# UC3842_-_SIN_TEST_GENERA_MODELO.net
KiCad netlist of a schematic drawn in Altium Designer
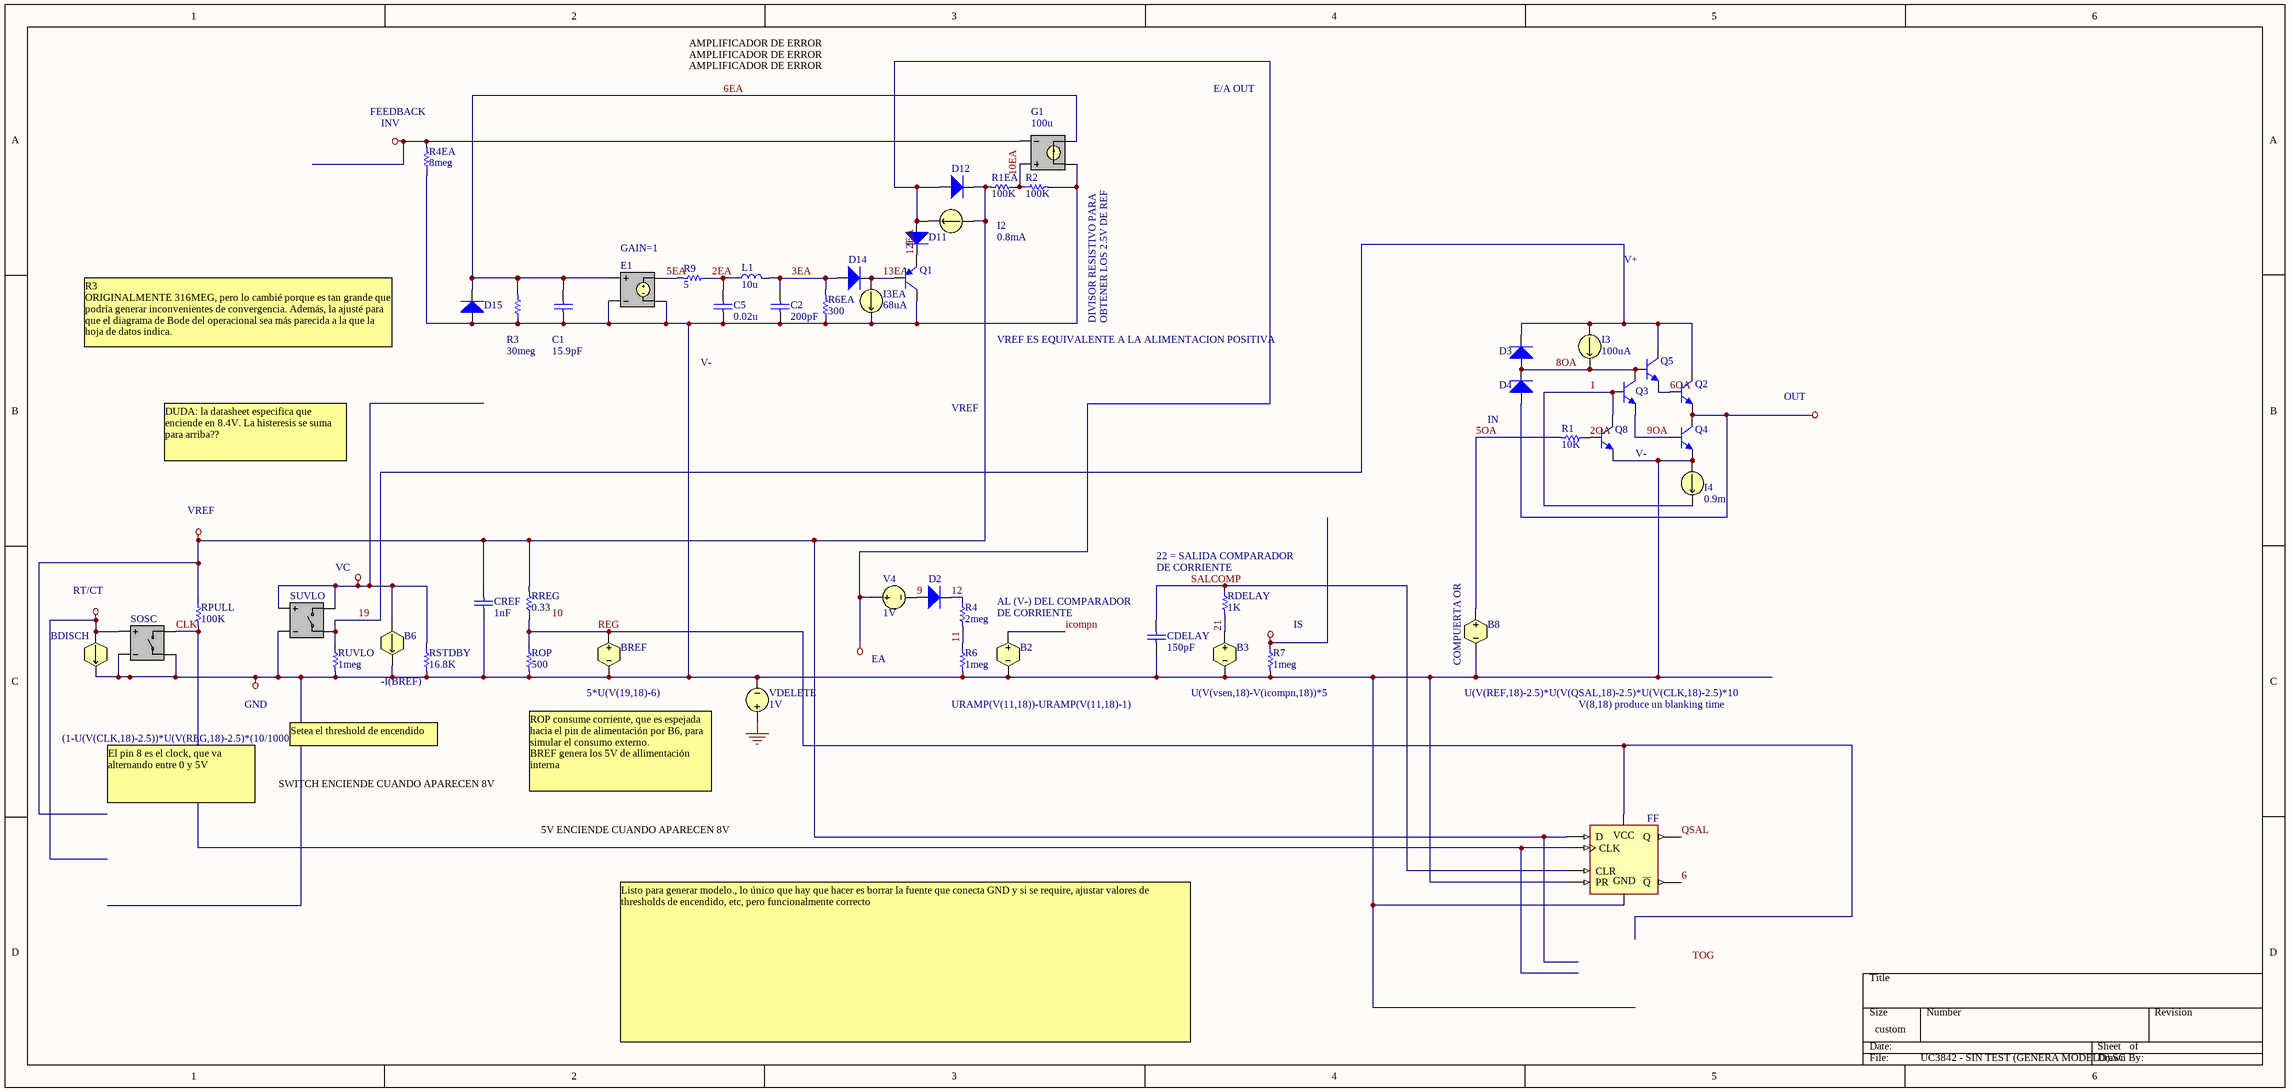
[diagram p0: UC3842 - SIN TEST (GENERA MODELO).SCHDOC]

(export (version "E")
  (design (tool "Eeschema 10.0.6"))
  (components
    (comp (ref "B2")
      (value "BVSRC")
      (description "Non-Linear Dependent Voltage Source")
      (fields
        (field (name "EQUATION") "URAMP(V(11,18))-URAMP(V(11,18)-1)")
        (field (name "PUBLISHER") "Altium Limited")
      )
      (libsource (lib "Simulation Sources") (part "BVSRC"))
    )
    (comp (ref "B3")
      (value "BVSRC")
      (description "Non-Linear Dependent Voltage Source")
      (fields
        (field (name "EQUATION") "U(V(vsen,18)-V(icompn,18))*5")
        (field (name "PUBLISHER") "Altium Limited")
      )
      (libsource (lib "Simulation Sources") (part "BVSRC"))
    )
    (comp (ref "B6")
      (value "BISRC")
      (description "Non-Linear Dependent Current Source")
      (fields (field (name "EQUATION") "-I(BREF)") (field (name "PUBLISHER") "Altium Limited"))
      (libsource (lib "Simulation Sources") (part "BISRC"))
    )
    (comp (ref "B8")
      (value "BVSRC")
      (description "Non-Linear Dependent Voltage Source")
      (fields
        (field (name "EQUATION") "U(V(REF,18)-2.5)*U(V(QSAL,18)-2.5)*U(V(CLK,18)-2.5)*10")
        (field (name "PUBLISHER") "Altium Limited")
      )
      (libsource (lib "Simulation Sources") (part "BVSRC"))
    )
    (comp (ref "BDISCH")
      (value "BISRC")
      (description "Non-Linear Dependent Current Source")
      (fields
        (field (name "EQUATION") "(1-U(V(CLK,18)-2.5))*U(V(REG,18)-2.5)*(10/1000)")
        (field (name "PUBLISHER") "Altium Limited")
      )
      (libsource (lib "Simulation Sources") (part "BISRC"))
    )
    (comp (ref "BREF")
      (value "BVSRC")
      (description "Non-Linear Dependent Voltage Source")
      (fields (field (name "EQUATION") "5*U(V(19,18)-6)") (field (name "PUBLISHER") "Altium Limited"))
      (libsource (lib "Simulation Sources") (part "BVSRC"))
    )
    (comp (ref "C1")
      (value "15.9pF")
      (footprint "0805")
      (description "Capacitor")
      (fields (field (name "VOLTAGE") "50V") (field (name "Comment") "Cap"))
      (libsource (lib "FEDE") (part "Cap"))
    )
    (comp (ref "C2")
      (value "200pF")
      (footprint "0805")
      (description "Capacitor")
      (fields (field (name "VOLTAGE") "50V") (field (name "Comment") "Cap"))
      (libsource (lib "FEDE") (part "Cap"))
    )
    (comp (ref "C5")
      (value "0.02u")
      (footprint "0805")
      (description "Capacitor")
      (fields (field (name "VOLTAGE") "50V") (field (name "Comment") "Cap"))
      (libsource (lib "FEDE") (part "Cap"))
    )
    (comp (ref "CDELAY")
      (value "150pF")
      (footprint "0805")
      (description "Capacitor")
      (fields (field (name "VOLTAGE") "50V") (field (name "Comment") "Cap"))
      (libsource (lib "FEDE") (part "Cap"))
    )
    (comp (ref "CREF")
      (value "1nF")
      (footprint "0805")
      (description "Capacitor")
      (fields (field (name "VOLTAGE") "50V") (field (name "Comment") "Cap"))
      (libsource (lib "FEDE") (part "Cap"))
    )
    (comp (ref "D2")
      (value "Diode")
      (footprint "diode400")
      (description "Diodo")
      (libsource (lib "FEDE") (part "Diode"))
    )
    (comp (ref "D3")
      (value "Diode")
      (footprint "diode400")
      (description "Diodo")
      (libsource (lib "FEDE") (part "Diode"))
    )
    (comp (ref "D4")
      (value "Diode")
      (footprint "diode400")
      (description "Diodo")
      (libsource (lib "FEDE") (part "Diode"))
    )
    (comp (ref "D11")
      (value "Diode")
      (footprint "diode400")
      (description "Diodo")
      (libsource (lib "FEDE") (part "Diode"))
    )
    (comp (ref "D12")
      (value "Diode")
      (footprint "diode400")
      (description "Diodo")
      (libsource (lib "FEDE") (part "Diode"))
    )
    (comp (ref "D14")
      (value "Diode")
      (footprint "diode400")
      (description "Diodo")
      (libsource (lib "FEDE") (part "Diode"))
    )
    (comp (ref "D15")
      (value "Diode")
      (footprint "diode400")
      (description "Diodo")
      (libsource (lib "FEDE") (part "Diode"))
    )
    (comp (ref "E1")
      (value "ESRC")
      (description "Voltage Controlled Voltage Source")
      (fields (field (name "PUBLISHER") "Altium Limited"))
      (libsource (lib "Simulation Sources") (part "ESRC"))
    )
    (comp (ref "FF")
      (value "FFSRV2")
      (description "D-Type Positive-Edge-Triggered Flip-Flop with Clear and Preset (simulación)")
      (libsource (lib "FEDE") (part "FFSRV2"))
    )
    (comp (ref "G1")
      (value "GSRC")
      (description "Voltage Controlled Current Source")
      (fields (field (name "GAIN") "100u") (field (name "PUBLISHER") "Altium Limited"))
      (libsource (lib "Simulation Sources") (part "GSRC"))
    )
    (comp (ref "I2")
      (value "0.8mA")
      (description "Current Source")
      (fields (field (name "Comment") "ISRC") (field (name "PUBLISHER") "Altium Limited"))
      (libsource (lib "Simulation Sources") (part "ISRC"))
    )
    (comp (ref "I3")
      (value "100uA")
      (description "Current Source")
      (fields (field (name "Comment") "ISRC") (field (name "PUBLISHER") "Altium Limited"))
      (libsource (lib "Simulation Sources") (part "ISRC"))
    )
    (comp (ref "I3EA")
      (value "68uA")
      (description "Current Source")
      (fields (field (name "Comment") "ISRC") (field (name "PUBLISHER") "Altium Limited"))
      (libsource (lib "Simulation Sources") (part "ISRC"))
    )
    (comp (ref "I4")
      (value "0.9m")
      (description "Current Source")
      (fields (field (name "Comment") "ISRC") (field (name "PUBLISHER") "Altium Limited"))
      (libsource (lib "Simulation Sources") (part "ISRC"))
    )
    (comp (ref "L1")
      (value "10u")
      (footprint "TOROIDE TN14-9-5")
      (description "Inductor")
      (fields (field (name "Comment") "Inductor2"))
      (libsource (lib "FEDE") (part "Inductor2"))
    )
    (comp (ref "Q1")
      (value "PNP")
      (footprint "SOT23")
      (description "PNP Bipolar Transistor")
      (libsource (lib "FEDE") (part "PNP"))
    )
    (comp (ref "Q2")
      (value "NPN")
      (footprint "SOT23")
      (description "NPN Bipolar Transistor")
      (libsource (lib "FEDE") (part "NPN"))
    )
    (comp (ref "Q3")
      (value "NPN")
      (footprint "SOT23")
      (description "NPN Bipolar Transistor")
      (libsource (lib "FEDE") (part "NPN"))
    )
    (comp (ref "Q4")
      (value "NPN")
      (footprint "SOT23")
      (description "NPN Bipolar Transistor")
      (libsource (lib "FEDE") (part "NPN"))
    )
    (comp (ref "Q5")
      (value "NPN")
      (footprint "SOT23")
      (description "NPN Bipolar Transistor")
      (libsource (lib "FEDE") (part "NPN"))
    )
    (comp (ref "Q8")
      (value "NPN")
      (footprint "SOT23")
      (description "NPN Bipolar Transistor")
      (libsource (lib "FEDE") (part "NPN"))
    )
    (comp (ref "R1")
      (value "10K")
      (footprint "0805")
      (description "Resistor")
      (fields (field (name "POWER") "0.25W") (field (name "Comment") "Res"))
      (libsource (lib "FEDE") (part "Res"))
    )
    (comp (ref "R1EA")
      (value "100K")
      (footprint "0805")
      (description "Resistor")
      (fields (field (name "POWER") "0.25W") (field (name "Comment") "Res"))
      (libsource (lib "FEDE") (part "Res"))
    )
    (comp (ref "R2")
      (value "100K")
      (footprint "0805")
      (description "Resistor")
      (fields (field (name "POWER") "0.25W") (field (name "Comment") "Res"))
      (libsource (lib "FEDE") (part "Res"))
    )
    (comp (ref "R3")
      (value "30meg")
      (footprint "0805")
      (description "Resistor")
      (fields (field (name "POWER") "0.25W") (field (name "Comment") "Res"))
      (libsource (lib "FEDE") (part "Res"))
    )
    (comp (ref "R4")
      (value "2meg")
      (footprint "0805")
      (description "Resistor")
      (fields (field (name "POWER") "0.25W") (field (name "Comment") "Res"))
      (libsource (lib "FEDE") (part "Res"))
    )
    (comp (ref "R4EA")
      (value "8meg")
      (footprint "0805")
      (description "Resistor")
      (fields (field (name "POWER") "0.25W") (field (name "Comment") "Res"))
      (libsource (lib "FEDE") (part "Res"))
    )
    (comp (ref "R6")
      (value "1meg")
      (footprint "0805")
      (description "Resistor")
      (fields (field (name "POWER") "0.25W") (field (name "Comment") "Res"))
      (libsource (lib "FEDE") (part "Res"))
    )
    (comp (ref "R6EA")
      (value "300")
      (footprint "0805")
      (description "Resistor")
      (fields (field (name "POWER") "0.25W") (field (name "Comment") "Res"))
      (libsource (lib "FEDE") (part "Res"))
    )
    (comp (ref "R7")
      (value "1meg")
      (footprint "0805")
      (description "Resistor")
      (fields (field (name "POWER") "0.25W") (field (name "Comment") "Res"))
      (libsource (lib "FEDE") (part "Res"))
    )
    (comp (ref "R9")
      (value "5")
      (footprint "0805")
      (description "Resistor")
      (fields (field (name "POWER") "0.25W") (field (name "Comment") "Res"))
      (libsource (lib "FEDE") (part "Res"))
    )
    (comp (ref "RDELAY")
      (value "1K")
      (footprint "0805")
      (description "Resistor")
      (fields (field (name "POWER") "0.25W") (field (name "Comment") "Res"))
      (libsource (lib "FEDE") (part "Res"))
    )
    (comp (ref "ROP")
      (value "500")
      (footprint "0805")
      (description "Resistor")
      (fields (field (name "POWER") "0.25W") (field (name "Comment") "Res"))
      (libsource (lib "FEDE") (part "Res"))
    )
    (comp (ref "RPULL")
      (value "100K")
      (footprint "0805")
      (description "Resistor")
      (fields (field (name "POWER") "0.25W") (field (name "Comment") "Res"))
      (libsource (lib "FEDE") (part "Res"))
    )
    (comp (ref "RREG")
      (value "0.33")
      (footprint "0805")
      (description "Resistor")
      (fields (field (name "POWER") "0.25W") (field (name "Comment") "Res"))
      (libsource (lib "FEDE") (part "Res"))
    )
    (comp (ref "RSTDBY")
      (value "16.8K")
      (footprint "0805")
      (description "Resistor")
      (fields (field (name "POWER") "0.25W") (field (name "Comment") "Res"))
      (libsource (lib "FEDE") (part "Res"))
    )
    (comp (ref "RUVLO")
      (value "1meg")
      (footprint "0805")
      (description "Resistor")
      (fields (field (name "POWER") "0.25W") (field (name "Comment") "Res"))
      (libsource (lib "FEDE") (part "Res"))
    )
    (comp (ref "SOSC")
      (value "VSW")
      (description "Voltage Controlled Switch (simulación)")
      (libsource (lib "FEDE") (part "VSW"))
    )
    (comp (ref "SUVLO")
      (value "VSW")
      (description "Voltage Controlled Switch (simulación)")
      (libsource (lib "FEDE") (part "VSW"))
    )
    (comp (ref "V4")
      (value "1V")
      (description "Voltage Source")
      (fields (field (name "Comment") "VSRC") (field (name "PUBLISHER") "Altium Limited"))
      (libsource (lib "Simulation Sources") (part "VSRC"))
    )
    (comp (ref "VDELETE")
      (value "1V")
      (description "Voltage Source")
      (fields (field (name "Comment") "VSRC") (field (name "PUBLISHER") "Altium Limited"))
      (libsource (lib "Simulation Sources") (part "VSRC"))
    )
  )
  (nets
    (net (code "1") (name "/1") (class "Default")
      (node (ref "I4") (pin "2") (pinfunction "2_2") (pintype "passive"))
      (node (ref "Q3") (pin "2") (pinfunction "B_2") (pintype "passive"))
      (node (ref "Q8") (pin "1") (pinfunction "C_1") (pintype "passive"))
    )
    (net (code "2") (name "/2EA") (class "Default")
      (node (ref "C5") (pin "2") (pinfunction "2_2") (pintype "passive"))
      (node (ref "L1") (pin "1") (pinfunction "1_1") (pintype "passive"))
      (node (ref "R9") (pin "1") (pinfunction "1_1") (pintype "passive"))
    )
    (net (code "3") (name "/2OA") (class "Default")
      (node (ref "Q8") (pin "2") (pinfunction "B_2") (pintype "passive"))
      (node (ref "R1") (pin "1") (pinfunction "1_1") (pintype "passive"))
    )
    (net (code "4") (name "/3EA") (class "Default")
      (node (ref "C2") (pin "2") (pinfunction "2_2") (pintype "passive"))
      (node (ref "D14") (pin "1") (pinfunction "1_1") (pintype "passive"))
      (node (ref "L1") (pin "2") (pinfunction "2_2") (pintype "passive"))
      (node (ref "R6EA") (pin "2") (pinfunction "2_2") (pintype "passive"))
    )
    (net (code "5") (name "/5EA") (class "Default")
      (node (ref "E1") (pin "3") (pinfunction "N+_3") (pintype "passive"))
      (node (ref "R9") (pin "2") (pinfunction "2_2") (pintype "passive"))
    )
    (net (code "6") (name "/5OA") (class "Default")
      (node (ref "B8") (pin "1") (pinfunction "1_1") (pintype "passive"))
      (node (ref "R1") (pin "2") (pinfunction "2_2") (pintype "passive"))
    )
    (net (code "7") (name "/6") (class "Default")
      (node (ref "FF") (pin "6") (pinfunction "~{Q}_6") (pintype "output"))
    )
    (net (code "8") (name "/6EA") (class "Default")
      (node (ref "C1") (pin "2") (pinfunction "2_2") (pintype "passive"))
      (node (ref "D15") (pin "2") (pinfunction "2_2") (pintype "passive"))
      (node (ref "E1") (pin "1") (pinfunction "NC+_1") (pintype "passive"))
      (node (ref "G1") (pin "4") (pinfunction "N-_4") (pintype "passive"))
      (node (ref "R3") (pin "2") (pinfunction "2_2") (pintype "passive"))
    )
    (net (code "9") (name "/6OA") (class "Default")
      (node (ref "Q2") (pin "2") (pinfunction "B_2") (pintype "passive"))
      (node (ref "Q5") (pin "3") (pinfunction "E_3") (pintype "passive"))
    )
    (net (code "10") (name "/8OA") (class "Default")
      (node (ref "D3") (pin "1") (pinfunction "1_1") (pintype "passive"))
      (node (ref "D4") (pin "2") (pinfunction "2_2") (pintype "passive"))
      (node (ref "I3") (pin "2") (pinfunction "2_2") (pintype "passive"))
      (node (ref "Q3") (pin "1") (pinfunction "C_1") (pintype "passive"))
      (node (ref "Q5") (pin "2") (pinfunction "B_2") (pintype "passive"))
    )
    (net (code "11") (name "/9") (class "Default")
      (node (ref "D2") (pin "1") (pinfunction "1_1") (pintype "passive"))
      (node (ref "V4") (pin "2") (pinfunction "2_2") (pintype "passive"))
    )
    (net (code "12") (name "/9OA") (class "Default")
      (node (ref "Q3") (pin "3") (pinfunction "E_3") (pintype "passive"))
      (node (ref "Q4") (pin "2") (pinfunction "B_2") (pintype "passive"))
    )
    (net (code "14") (name "/10EA") (class "Default")
      (node (ref "G1") (pin "1") (pinfunction "NC+_1") (pintype "passive"))
      (node (ref "R1EA") (pin "1") (pinfunction "1_1") (pintype "passive"))
      (node (ref "R2") (pin "1") (pinfunction "1_1") (pintype "passive"))
    )
    (net (code "15") (name "/11") (class "Default")
      (node (ref "R4") (pin "2") (pinfunction "2_2") (pintype "passive"))
      (node (ref "R6") (pin "1") (pinfunction "1_1") (pintype "passive"))
    )
    (net (code "16") (name "/12") (class "Default")
      (node (ref "D2") (pin "2") (pinfunction "2_2") (pintype "passive"))
      (node (ref "R4") (pin "1") (pinfunction "1_1") (pintype "passive"))
    )
    (net (code "17") (name "/12EA") (class "Default")
      (node (ref "D11") (pin "2") (pinfunction "2_2") (pintype "passive"))
      (node (ref "Q1") (pin "3") (pinfunction "E_3") (pintype "passive"))
    )
    (net (code "18") (name "/13EA") (class "Default")
      (node (ref "D14") (pin "2") (pinfunction "2_2") (pintype "passive"))
      (node (ref "I3EA") (pin "1") (pinfunction "1_1") (pintype "passive"))
      (node (ref "Q1") (pin "2") (pinfunction "B_2") (pintype "passive"))
    )
    (net (code "19") (name "/19") (class "Default")
      (node (ref "D3") (pin "2") (pinfunction "2_2") (pintype "passive"))
      (node (ref "I3") (pin "1") (pinfunction "1_1") (pintype "passive"))
      (node (ref "Q2") (pin "1") (pinfunction "C_1") (pintype "passive"))
      (node (ref "Q5") (pin "1") (pinfunction "C_1") (pintype "passive"))
      (node (ref "RUVLO") (pin "1") (pinfunction "1_1") (pintype "passive"))
      (node (ref "SUVLO") (pin "4") (pinfunction "N2-_4") (pintype "passive"))
    )
    (net (code "20") (name "/21") (class "Default")
      (node (ref "B3") (pin "1") (pinfunction "1_1") (pintype "passive"))
      (node (ref "RDELAY") (pin "2") (pinfunction "2_2") (pintype "passive"))
    )
    (net (code "21") (name "/CLK") (class "Default")
      (node (ref "FF") (pin "3") (pinfunction "CLK_3") (pintype "input"))
      (node (ref "RPULL") (pin "2") (pinfunction "2_2") (pintype "passive"))
      (node (ref "SOSC") (pin "3") (pinfunction "N2+_3") (pintype "passive"))
    )
    (net (code "22") (name "/QSAL") (class "Default")
      (node (ref "FF") (pin "5") (pinfunction "Q_5") (pintype "output"))
    )
    (net (code "23") (name "/REG") (class "Default")
      (node (ref "BREF") (pin "1") (pinfunction "1_1") (pintype "passive"))
      (node (ref "FF") (pin "14") (pinfunction "VCC_14") (pintype "power_in"))
      (node (ref "ROP") (pin "1") (pinfunction "1_1") (pintype "passive"))
      (node (ref "RREG") (pin "1") (pinfunction "1_1") (pintype "passive"))
    )
    (net (code "24") (name "/SALCOMP") (class "Default")
      (node (ref "CDELAY") (pin "2") (pinfunction "2_2") (pintype "passive"))
      (node (ref "FF") (pin "1") (pinfunction "CLR_1") (pintype "input"))
      (node (ref "RDELAY") (pin "1") (pinfunction "1_1") (pintype "passive"))
    )
    (net (code "26") (name "/icompn") (class "Default")
      (node (ref "B2") (pin "1") (pinfunction "1_1") (pintype "passive"))
    )
    (net (code "27") (name "18") (class "Default")
      (node (ref "B2") (pin "2") (pinfunction "2_2") (pintype "passive"))
      (node (ref "B3") (pin "2") (pinfunction "2_2") (pintype "passive"))
      (node (ref "B6") (pin "2") (pinfunction "2_2") (pintype "passive"))
      (node (ref "B8") (pin "2") (pinfunction "2_2") (pintype "passive"))
      (node (ref "BDISCH") (pin "2") (pinfunction "2_2") (pintype "passive"))
      (node (ref "BREF") (pin "2") (pinfunction "2_2") (pintype "passive"))
      (node (ref "C1") (pin "1") (pinfunction "1_1") (pintype "passive"))
      (node (ref "C2") (pin "1") (pinfunction "1_1") (pintype "passive"))
      (node (ref "C5") (pin "1") (pinfunction "1_1") (pintype "passive"))
      (node (ref "CDELAY") (pin "1") (pinfunction "1_1") (pintype "passive"))
      (node (ref "CREF") (pin "1") (pinfunction "1_1") (pintype "passive"))
      (node (ref "D15") (pin "1") (pinfunction "1_1") (pintype "passive"))
      (node (ref "E1") (pin "2") (pinfunction "NC-_2") (pintype "passive"))
      (node (ref "E1") (pin "4") (pinfunction "N-_4") (pintype "passive"))
      (node (ref "FF") (pin "4") (pinfunction "PR_4") (pintype "input"))
      (node (ref "FF") (pin "7") (pinfunction "GND_7") (pintype "power_in"))
      (node (ref "G1") (pin "3") (pinfunction "N+_3") (pintype "passive"))
      (node (ref "I3EA") (pin "2") (pinfunction "2_2") (pintype "passive"))
      (node (ref "I4") (pin "1") (pinfunction "1_1") (pintype "passive"))
      (node (ref "Q1") (pin "1") (pinfunction "C_1") (pintype "passive"))
      (node (ref "Q4") (pin "3") (pinfunction "E_3") (pintype "passive"))
      (node (ref "Q8") (pin "3") (pinfunction "E_3") (pintype "passive"))
      (node (ref "R2") (pin "2") (pinfunction "2_2") (pintype "passive"))
      (node (ref "R3") (pin "1") (pinfunction "1_1") (pintype "passive"))
      (node (ref "R4EA") (pin "1") (pinfunction "1_1") (pintype "passive"))
      (node (ref "R6") (pin "2") (pinfunction "2_2") (pintype "passive"))
      (node (ref "R6EA") (pin "1") (pinfunction "1_1") (pintype "passive"))
      (node (ref "R7") (pin "2") (pinfunction "2_2") (pintype "passive"))
      (node (ref "ROP") (pin "2") (pinfunction "2_2") (pintype "passive"))
      (node (ref "RSTDBY") (pin "2") (pinfunction "2_2") (pintype "passive"))
      (node (ref "RUVLO") (pin "2") (pinfunction "2_2") (pintype "passive"))
      (node (ref "SOSC") (pin "2") (pinfunction "N1-_2") (pintype "passive"))
      (node (ref "SOSC") (pin "4") (pinfunction "N2-_4") (pintype "passive"))
      (node (ref "SUVLO") (pin "2") (pinfunction "N1-_2") (pintype "passive"))
      (node (ref "VDELETE") (pin "2") (pinfunction "2_2") (pintype "passive"))
    )
    (net (code "28") (name "ALIM") (class "Default")
      (node (ref "B6") (pin "1") (pinfunction "1_1") (pintype "passive"))
      (node (ref "RSTDBY") (pin "1") (pinfunction "1_1") (pintype "passive"))
      (node (ref "SUVLO") (pin "1") (pinfunction "N1+_1") (pintype "passive"))
      (node (ref "SUVLO") (pin "3") (pinfunction "N2+_3") (pintype "passive"))
    )
    (net (code "29") (name "EAOUTP") (class "Default")
      (node (ref "D11") (pin "1") (pinfunction "1_1") (pintype "passive"))
      (node (ref "D12") (pin "1") (pinfunction "1_1") (pintype "passive"))
      (node (ref "I2") (pin "2") (pinfunction "2_2") (pintype "passive"))
      (node (ref "V4") (pin "1") (pinfunction "1_1") (pintype "passive"))
    )
    (net (code "30") (name "FEED") (class "Default")
      (node (ref "G1") (pin "2") (pinfunction "NC-_2") (pintype "passive"))
      (node (ref "R4EA") (pin "2") (pinfunction "2_2") (pintype "passive"))
    )
    (net (code "31") (name "GND") (class "Default")
      (node (ref "VDELETE") (pin "1") (pinfunction "1_1") (pintype "passive"))
    )
    (net (code "32") (name "OUTP") (class "Default")
      (node (ref "D4") (pin "1") (pinfunction "1_1") (pintype "passive"))
      (node (ref "Q2") (pin "3") (pinfunction "E_3") (pintype "passive"))
      (node (ref "Q4") (pin "1") (pinfunction "C_1") (pintype "passive"))
    )
    (net (code "33") (name "REF") (class "Default")
      (node (ref "CREF") (pin "2") (pinfunction "2_2") (pintype "passive"))
      (node (ref "D12") (pin "2") (pinfunction "2_2") (pintype "passive"))
      (node (ref "FF") (pin "2") (pinfunction "D_2") (pintype "input"))
      (node (ref "I2") (pin "1") (pinfunction "1_1") (pintype "passive"))
      (node (ref "R1EA") (pin "2") (pinfunction "2_2") (pintype "passive"))
      (node (ref "RPULL") (pin "1") (pinfunction "1_1") (pintype "passive"))
      (node (ref "RREG") (pin "2") (pinfunction "2_2") (pintype "passive"))
    )
    (net (code "34") (name "RTCT") (class "Default")
      (node (ref "BDISCH") (pin "1") (pinfunction "1_1") (pintype "passive"))
      (node (ref "SOSC") (pin "1") (pinfunction "N1+_1") (pintype "passive"))
    )
    (net (code "35") (name "VSEN") (class "Default")
      (node (ref "R7") (pin "1") (pinfunction "1_1") (pintype "passive"))
    )
  )
)
